# modFOC-RC-Interface.net
KiCad netlist of a schematic drawn in Altium Designer
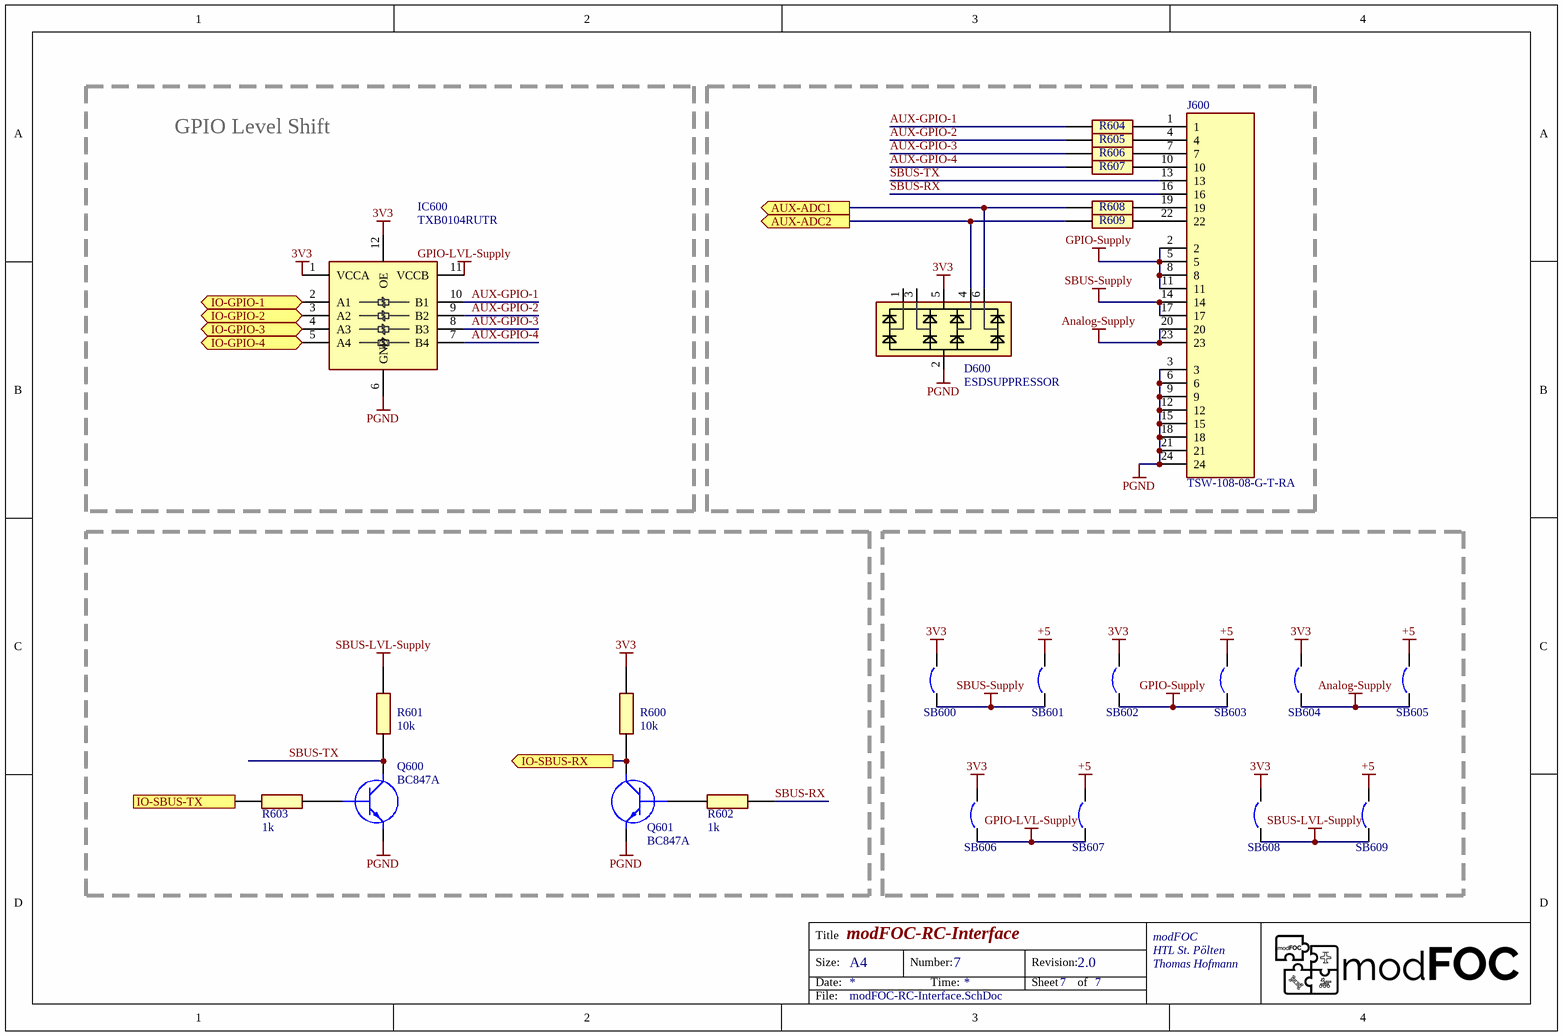
[diagram p0: modFOC-RC-Interface.SchDoc]

(export (version "E")
  (design (tool "Eeschema 10.0.6"))
  (components
    (comp (ref "D600")
      (value "ESDSUPPRESSOR")
      (footprint "SOT23-6")
      (description "TVS Diode Array")
      (libsource (lib "RcMPPTLib") (part "ESDSUPPRESSOR"))
    )
    (comp (ref "IC600")
      (value "TXB0104RUTR")
      (footprint "TXB0104RUTR")
      (description "Integrated Circuit")
      (fields (field (name "MOUSER PART NUMBER") "595-TXB0104RUTR"))
      (libsource (lib "RcMPPTLib") (part "TXB0104RUTR"))
    )
    (comp (ref "J600")
      (value "TSW-108-08-G-T-RA")
      (footprint "HDRRA24W64P254_3X8_2032X254X812P")
      (description "Connector")
      (fields (field (name "MOUSER PART NUMBER") "200-TSW10808GTRA"))
      (libsource (lib "RcMPPTLib") (part "TSW-108-08-G-T-RA"))
    )
    (comp (ref "Q600")
      (value "BC847A")
      (footprint "SOT95P230X110-3N")
      (description "Transistor BJT NPN")
      (fields
        (field (name "MANUFACTURER_PART_NUMBER") "BC847A,235")
        (field (name "MOUSER PART NUMBER") "771-BC847A235")
      )
      (libsource (lib "RcMPPTLib") (part "BC847A,235"))
    )
    (comp (ref "Q601")
      (value "BC847A")
      (footprint "SOT95P230X110-3N")
      (description "Transistor BJT NPN")
      (fields
        (field (name "MANUFACTURER_PART_NUMBER") "BC847A,235")
        (field (name "MOUSER PART NUMBER") "771-BC847A235")
      )
      (libsource (lib "RcMPPTLib") (part "BC847A,235"))
    )
    (comp (ref "R600")
      (value "10k")
      (footprint "RESC1608X50N")
      (description "Resistor")
      (libsource (lib "") (part "R0603_2"))
    )
    (comp (ref "R601")
      (value "10k")
      (footprint "RESC1608X50N")
      (description "Resistor")
      (libsource (lib "") (part "R0603_1"))
    )
    (comp (ref "R602")
      (value "1k")
      (footprint "RESC1608X50N")
      (description "Resistor")
      (libsource (lib "") (part "R0603_1"))
    )
    (comp (ref "R603")
      (value "1k")
      (footprint "RESC1608X50N")
      (description "Resistor")
      (libsource (lib "RcMPPTLib") (part "R0603"))
    )
    (comp (ref "R604")
      (value "100R")
      (footprint "RESC1005X40N")
      (description "Resistor")
      (libsource (lib "RcMPPTLib") (part "R0402"))
    )
    (comp (ref "R605")
      (value "100R")
      (footprint "RESC1005X40N")
      (description "Resistor")
      (libsource (lib "RcMPPTLib") (part "R0402"))
    )
    (comp (ref "R606")
      (value "100R")
      (footprint "RESC1005X40N")
      (description "Resistor")
      (libsource (lib "RcMPPTLib") (part "R0402"))
    )
    (comp (ref "R607")
      (value "100R")
      (footprint "RESC1005X40N")
      (description "Resistor")
      (libsource (lib "RcMPPTLib") (part "R0402"))
    )
    (comp (ref "R608")
      (value "100R")
      (footprint "RESC1005X40N")
      (description "Resistor")
      (libsource (lib "RcMPPTLib") (part "R0402"))
    )
    (comp (ref "R609")
      (value "100R")
      (footprint "RESC1005X40N")
      (description "Resistor")
      (libsource (lib "RcMPPTLib") (part "R0402"))
    )
    (comp (ref "SB600")
      (value "Solder Bridge")
      (footprint "SB0402")
      (fields
        (field (name "INTERNAL_PART_NUMBER") "MCD-00071")
        (field (name "MANUFACTURER_PART_NUMBER") "RC0603JR-070RL")
        (field (name "MANUFACTURER") "YAGEO")
        (field (name "PROVIDED_BY") "SUBCO")
      )
      (libsource (lib "Schlib1") (part "Solder Bridge"))
    )
    (comp (ref "SB601")
      (value "Solder Bridge")
      (footprint "SB0402")
      (fields
        (field (name "INTERNAL_PART_NUMBER") "MCD-00071")
        (field (name "MANUFACTURER_PART_NUMBER") "RC0603JR-070RL")
        (field (name "MANUFACTURER") "YAGEO")
        (field (name "PROVIDED_BY") "SUBCO")
      )
      (libsource (lib "Schlib1") (part "Solder Bridge"))
    )
    (comp (ref "SB602")
      (value "Solder Bridge")
      (footprint "SB0402")
      (fields
        (field (name "INTERNAL_PART_NUMBER") "MCD-00071")
        (field (name "MANUFACTURER_PART_NUMBER") "RC0603JR-070RL")
        (field (name "MANUFACTURER") "YAGEO")
        (field (name "PROVIDED_BY") "SUBCO")
      )
      (libsource (lib "Schlib1") (part "Solder Bridge"))
    )
    (comp (ref "SB603")
      (value "Solder Bridge")
      (footprint "SB0402")
      (fields
        (field (name "INTERNAL_PART_NUMBER") "MCD-00071")
        (field (name "MANUFACTURER_PART_NUMBER") "RC0603JR-070RL")
        (field (name "MANUFACTURER") "YAGEO")
        (field (name "PROVIDED_BY") "SUBCO")
      )
      (libsource (lib "Schlib1") (part "Solder Bridge"))
    )
    (comp (ref "SB604")
      (value "Solder Bridge")
      (footprint "SB0402")
      (fields
        (field (name "INTERNAL_PART_NUMBER") "MCD-00071")
        (field (name "MANUFACTURER_PART_NUMBER") "RC0603JR-070RL")
        (field (name "MANUFACTURER") "YAGEO")
        (field (name "PROVIDED_BY") "SUBCO")
      )
      (libsource (lib "Schlib1") (part "Solder Bridge"))
    )
    (comp (ref "SB605")
      (value "Solder Bridge")
      (footprint "SB0402")
      (fields
        (field (name "INTERNAL_PART_NUMBER") "MCD-00071")
        (field (name "MANUFACTURER_PART_NUMBER") "RC0603JR-070RL")
        (field (name "MANUFACTURER") "YAGEO")
        (field (name "PROVIDED_BY") "SUBCO")
      )
      (libsource (lib "Schlib1") (part "Solder Bridge"))
    )
    (comp (ref "SB606")
      (value "Solder Bridge")
      (footprint "SB0402")
      (fields
        (field (name "INTERNAL_PART_NUMBER") "MCD-00071")
        (field (name "MANUFACTURER_PART_NUMBER") "RC0603JR-070RL")
        (field (name "MANUFACTURER") "YAGEO")
        (field (name "PROVIDED_BY") "SUBCO")
      )
      (libsource (lib "Schlib1") (part "Solder Bridge"))
    )
    (comp (ref "SB607")
      (value "Solder Bridge")
      (footprint "SB0402")
      (fields
        (field (name "INTERNAL_PART_NUMBER") "MCD-00071")
        (field (name "MANUFACTURER_PART_NUMBER") "RC0603JR-070RL")
        (field (name "MANUFACTURER") "YAGEO")
        (field (name "PROVIDED_BY") "SUBCO")
      )
      (libsource (lib "Schlib1") (part "Solder Bridge"))
    )
    (comp (ref "SB608")
      (value "Solder Bridge")
      (footprint "SB0402")
      (fields
        (field (name "INTERNAL_PART_NUMBER") "MCD-00071")
        (field (name "MANUFACTURER_PART_NUMBER") "RC0603JR-070RL")
        (field (name "MANUFACTURER") "YAGEO")
        (field (name "PROVIDED_BY") "SUBCO")
      )
      (libsource (lib "Schlib1") (part "Solder Bridge"))
    )
    (comp (ref "SB609")
      (value "Solder Bridge")
      (footprint "SB0402")
      (fields
        (field (name "INTERNAL_PART_NUMBER") "MCD-00071")
        (field (name "MANUFACTURER_PART_NUMBER") "RC0603JR-070RL")
        (field (name "MANUFACTURER") "YAGEO")
        (field (name "PROVIDED_BY") "SUBCO")
      )
      (libsource (lib "Schlib1") (part "Solder Bridge"))
    )
  )
  (nets
    (net (code "1") (name "+5") (class "Default")
      (node (ref "SB601") (pin "2") (pinfunction "2_2") (pintype "passive"))
      (node (ref "SB603") (pin "2") (pinfunction "2_2") (pintype "passive"))
      (node (ref "SB605") (pin "2") (pinfunction "2_2") (pintype "passive"))
      (node (ref "SB607") (pin "2") (pinfunction "2_2") (pintype "passive"))
      (node (ref "SB609") (pin "2") (pinfunction "2_2") (pintype "passive"))
    )
    (net (code "2") (name "/AUX-ADC1") (class "Default")
      (node (ref "D600") (pin "6") (pinfunction "CH4_6") (pintype "passive"))
      (node (ref "R608") (pin "1") (pinfunction "1_1") (pintype "passive"))
    )
    (net (code "3") (name "/AUX-ADC2") (class "Default")
      (node (ref "D600") (pin "4") (pinfunction "CH3_4") (pintype "passive"))
      (node (ref "R609") (pin "1") (pinfunction "1_1") (pintype "passive"))
    )
    (net (code "4") (name "/AUX-GPIO-1") (class "Default")
      (node (ref "IC600") (pin "10") (pinfunction "B1_10") (pintype "passive"))
      (node (ref "R604") (pin "1") (pinfunction "1_1") (pintype "passive"))
    )
    (net (code "5") (name "/AUX-GPIO-2") (class "Default")
      (node (ref "IC600") (pin "9") (pinfunction "B2_9") (pintype "passive"))
      (node (ref "R605") (pin "1") (pinfunction "1_1") (pintype "passive"))
    )
    (net (code "6") (name "/AUX-GPIO-3") (class "Default")
      (node (ref "IC600") (pin "8") (pinfunction "B3_8") (pintype "passive"))
      (node (ref "R606") (pin "1") (pinfunction "1_1") (pintype "passive"))
    )
    (net (code "7") (name "/AUX-GPIO-4") (class "Default")
      (node (ref "IC600") (pin "7") (pinfunction "B4_7") (pintype "passive"))
      (node (ref "R607") (pin "1") (pinfunction "1_1") (pintype "passive"))
    )
    (net (code "8") (name "/IO-GPIO-1") (class "Default")
      (node (ref "IC600") (pin "2") (pinfunction "A1_2") (pintype "passive"))
    )
    (net (code "9") (name "/IO-GPIO-2") (class "Default")
      (node (ref "IC600") (pin "3") (pinfunction "A2_3") (pintype "passive"))
    )
    (net (code "10") (name "/IO-GPIO-3") (class "Default")
      (node (ref "IC600") (pin "4") (pinfunction "A3_4") (pintype "passive"))
    )
    (net (code "11") (name "/IO-GPIO-4") (class "Default")
      (node (ref "IC600") (pin "5") (pinfunction "A4_5") (pintype "passive"))
    )
    (net (code "12") (name "/IO-SBUS-RX") (class "Default")
      (node (ref "Q601") (pin "3") (pinfunction "C_3") (pintype "passive"))
      (node (ref "R600") (pin "1") (pinfunction "1_1") (pintype "passive"))
    )
    (net (code "13") (name "/IO-SBUS-TX") (class "Default")
      (node (ref "R603") (pin "2") (pinfunction "2_2") (pintype "passive"))
    )
    (net (code "14") (name "/SBUS-RX") (class "Default")
      (node (ref "J600") (pin "16") (pinfunction "16_16") (pintype "passive"))
      (node (ref "R602") (pin "2") (pinfunction "2_2") (pintype "passive"))
    )
    (net (code "15") (name "/SBUS-TX") (class "Default")
      (node (ref "J600") (pin "13") (pinfunction "13_13") (pintype "passive"))
      (node (ref "Q600") (pin "3") (pinfunction "C_3") (pintype "passive"))
      (node (ref "R601") (pin "1") (pinfunction "1_1") (pintype "passive"))
    )
    (net (code "16") (name "3V3") (class "Default")
      (node (ref "D600") (pin "5") (pinfunction "VDD_5") (pintype "passive"))
      (node (ref "IC600") (pin "1") (pinfunction "VCCA_1") (pintype "passive"))
      (node (ref "IC600") (pin "12") (pinfunction "OE_12") (pintype "passive"))
      (node (ref "R600") (pin "2") (pinfunction "2_2") (pintype "passive"))
      (node (ref "SB600") (pin "2") (pinfunction "2_2") (pintype "passive"))
      (node (ref "SB602") (pin "2") (pinfunction "2_2") (pintype "passive"))
      (node (ref "SB604") (pin "2") (pinfunction "2_2") (pintype "passive"))
      (node (ref "SB606") (pin "2") (pinfunction "2_2") (pintype "passive"))
      (node (ref "SB608") (pin "2") (pinfunction "2_2") (pintype "passive"))
    )
    (net (code "17") (name "Analog-Supply") (class "Default")
      (node (ref "J600") (pin "20") (pinfunction "20_20") (pintype "passive"))
      (node (ref "J600") (pin "23") (pinfunction "23_23") (pintype "passive"))
      (node (ref "SB604") (pin "1") (pinfunction "1_1") (pintype "passive"))
      (node (ref "SB605") (pin "1") (pinfunction "1_1") (pintype "passive"))
    )
    (net (code "18") (name "GPIO-LVL-Supply") (class "Default")
      (node (ref "IC600") (pin "11") (pinfunction "VCCB_11") (pintype "passive"))
      (node (ref "SB606") (pin "1") (pinfunction "1_1") (pintype "passive"))
      (node (ref "SB607") (pin "1") (pinfunction "1_1") (pintype "passive"))
    )
    (net (code "19") (name "GPIO-Supply") (class "Default")
      (node (ref "J600") (pin "11") (pinfunction "11_11") (pintype "passive"))
      (node (ref "J600") (pin "2") (pinfunction "2_2") (pintype "passive"))
      (node (ref "J600") (pin "5") (pinfunction "5_5") (pintype "passive"))
      (node (ref "J600") (pin "8") (pinfunction "8_8") (pintype "passive"))
      (node (ref "SB602") (pin "1") (pinfunction "1_1") (pintype "passive"))
      (node (ref "SB603") (pin "1") (pinfunction "1_1") (pintype "passive"))
    )
    (net (code "20") (name "Net-(J600-Pad1)") (class "Default")
      (node (ref "J600") (pin "1") (pinfunction "1_1") (pintype "passive"))
      (node (ref "R604") (pin "2") (pinfunction "2_2") (pintype "passive"))
    )
    (net (code "21") (name "Net-(J600-Pad4)") (class "Default")
      (node (ref "J600") (pin "4") (pinfunction "4_4") (pintype "passive"))
      (node (ref "R605") (pin "2") (pinfunction "2_2") (pintype "passive"))
    )
    (net (code "22") (name "Net-(J600-Pad7)") (class "Default")
      (node (ref "J600") (pin "7") (pinfunction "7_7") (pintype "passive"))
      (node (ref "R606") (pin "2") (pinfunction "2_2") (pintype "passive"))
    )
    (net (code "23") (name "Net-(J600-Pad10)") (class "Default")
      (node (ref "J600") (pin "10") (pinfunction "10_10") (pintype "passive"))
      (node (ref "R607") (pin "2") (pinfunction "2_2") (pintype "passive"))
    )
    (net (code "24") (name "Net-(J600-Pad19)") (class "Default")
      (node (ref "J600") (pin "19") (pinfunction "19_19") (pintype "passive"))
      (node (ref "R608") (pin "2") (pinfunction "2_2") (pintype "passive"))
    )
    (net (code "25") (name "Net-(J600-Pad22)") (class "Default")
      (node (ref "J600") (pin "22") (pinfunction "22_22") (pintype "passive"))
      (node (ref "R609") (pin "2") (pinfunction "2_2") (pintype "passive"))
    )
    (net (code "26") (name "Net-(Q600-B)") (class "Default")
      (node (ref "Q600") (pin "1") (pinfunction "B_1") (pintype "passive"))
      (node (ref "R603") (pin "1") (pinfunction "1_1") (pintype "passive"))
    )
    (net (code "27") (name "Net-(Q601-B)") (class "Default")
      (node (ref "Q601") (pin "1") (pinfunction "B_1") (pintype "passive"))
      (node (ref "R602") (pin "1") (pinfunction "1_1") (pintype "passive"))
    )
    (net (code "28") (name "PGND") (class "Default")
      (node (ref "D600") (pin "2") (pinfunction "GND_2") (pintype "passive"))
      (node (ref "IC600") (pin "6") (pinfunction "GND_6") (pintype "passive"))
      (node (ref "J600") (pin "12") (pinfunction "12_12") (pintype "passive"))
      (node (ref "J600") (pin "15") (pinfunction "15_15") (pintype "passive"))
      (node (ref "J600") (pin "18") (pinfunction "18_18") (pintype "passive"))
      (node (ref "J600") (pin "21") (pinfunction "21_21") (pintype "passive"))
      (node (ref "J600") (pin "24") (pinfunction "24_24") (pintype "passive"))
      (node (ref "J600") (pin "3") (pinfunction "3_3") (pintype "passive"))
      (node (ref "J600") (pin "6") (pinfunction "6_6") (pintype "passive"))
      (node (ref "J600") (pin "9") (pinfunction "9_9") (pintype "passive"))
      (node (ref "Q600") (pin "2") (pinfunction "E_2") (pintype "passive"))
      (node (ref "Q601") (pin "2") (pinfunction "E_2") (pintype "passive"))
    )
    (net (code "29") (name "SBUS-LVL-Supply") (class "Default")
      (node (ref "R601") (pin "2") (pinfunction "2_2") (pintype "passive"))
      (node (ref "SB608") (pin "1") (pinfunction "1_1") (pintype "passive"))
      (node (ref "SB609") (pin "1") (pinfunction "1_1") (pintype "passive"))
    )
    (net (code "30") (name "SBUS-Supply") (class "Default")
      (node (ref "J600") (pin "14") (pinfunction "14_14") (pintype "passive"))
      (node (ref "J600") (pin "17") (pinfunction "17_17") (pintype "passive"))
      (node (ref "SB600") (pin "1") (pinfunction "1_1") (pintype "passive"))
      (node (ref "SB601") (pin "1") (pinfunction "1_1") (pintype "passive"))
    )
    (net (code "31") (name "unconnected-(D600-CH1-Pad1)") (class "Default")
      (node (ref "D600") (pin "1") (pinfunction "CH1_1") (pintype "passive"))
    )
    (net (code "32") (name "unconnected-(D600-CH2-Pad3)") (class "Default")
      (node (ref "D600") (pin "3") (pinfunction "CH2_3") (pintype "passive"))
    )
  )
)
